# Optocoupler.net
KiCad netlist of a schematic drawn in Altium Designer
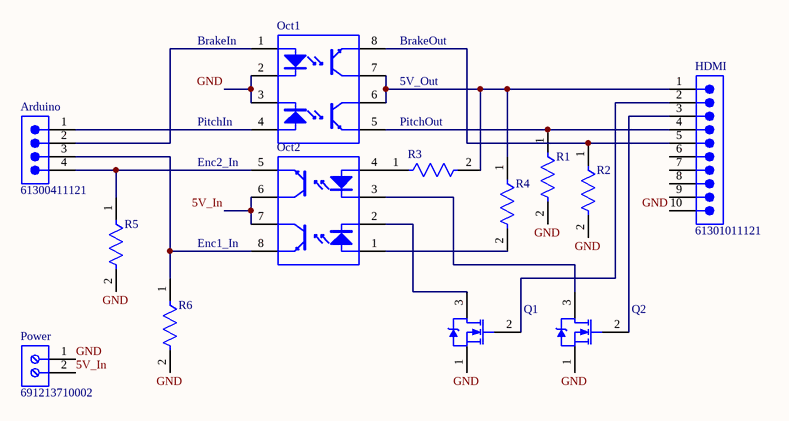
[diagram p0: Optocoupler.SchDoc]

(export (version "E")
  (design (tool "Eeschema 10.0.6"))
  (components
    (comp (ref "Arduino")
      (value "61300411121")
      (footprint "61300411121")
      (libsource (lib "Altium Content Vault") (part "Header_Male_1R_04P"))
    )
    (comp (ref "HDMI")
      (value "61301011121")
      (footprint "61301011121")
      (libsource (lib "Altium Content Vault") (part "Header_Male_1R_10P"))
    )
    (comp (ref "Oct1")
      (value "~")
      (footprint "VISH-DIP8")
      (description "Optocoupler, Phototransistor Output, Dual Channel, 1.3 V, -55 to 100 degC, 8-Pin DIP, RoHS, Tube")
      (fields (field (name "TOLERANCE") "1%"))
      (libsource (lib "Altium Content Vault") (part "OPTO-AKKAECCE-8"))
    )
    (comp (ref "Oct2")
      (value "~")
      (footprint "VISH-DIP8")
      (description "Optocoupler, Phototransistor Output, Dual Channel, 1.3 V, -55 to 100 degC, 8-Pin DIP, RoHS, Tube")
      (fields (field (name "TOLERANCE") "1%"))
      (libsource (lib "Altium Content Vault") (part "OPTO-AKKAECCE-8"))
    )
    (comp (ref "Power")
      (value "691213710002")
      (footprint "691213710002")
      (fields (field (name "VOLTAGE") "300V"))
      (libsource (lib "Altium Content Vault") (part "TBL - 1R - 02P - Screw"))
    )
    (comp (ref "Q1")
      (value "~")
      (footprint "ONSC-TO-92-3-29-11_AM_BL")
      (description "Small Signal MOSFET, 200 mA, 60 V, N-Channel, 3-Pin TO-92, Pb-Free, Tape and Reel")
      (fields (field (name "MANUFACTURER") "On Semiconductor") (field (name "PARTNUMBER") "2N7000RLRAG"))
      (libsource (lib "Altium Content Vault") (part "ONSC-NMOS-S1G2D3-3"))
    )
    (comp (ref "Q2")
      (value "~")
      (footprint "ONSC-TO-92-3-29-11_AM_BL")
      (description "Small Signal MOSFET, 200 mA, 60 V, N-Channel, 3-Pin TO-92, Pb-Free, Tape and Reel")
      (fields (field (name "MANUFACTURER") "On Semiconductor") (field (name "PARTNUMBER") "2N7000RLRAG"))
      (libsource (lib "Altium Content Vault") (part "ONSC-NMOS-S1G2D3-3"))
    )
    (comp (ref "R1")
      (value "~")
      (footprint "FP-MRS25-MFG")
      (fields (field (name "TOLERANCE") "1%"))
      (libsource (lib "Altium Content Vault") (part "1029c3af85768c4190bb7ad29bc67b5"))
    )
    (comp (ref "R2")
      (value "~")
      (footprint "FP-MRS25-MFG")
      (fields (field (name "TOLERANCE") "1%"))
      (libsource (lib "Altium Content Vault") (part "1029c3af85768c4190bb7ad29bc67b5"))
    )
    (comp (ref "R3")
      (value "~")
      (footprint "FP-MRS25-MFG")
      (fields (field (name "TOLERANCE") "1%"))
      (libsource (lib "Altium Content Vault") (part "1029c3af85768c4190bb7ad29bc67b5"))
    )
    (comp (ref "R4")
      (value "~")
      (footprint "FP-MRS25-MFG")
      (fields (field (name "TOLERANCE") "1%"))
      (libsource (lib "Altium Content Vault") (part "1029c3af85768c4190bb7ad29bc67b5"))
    )
    (comp (ref "R5")
      (value "~")
      (footprint "FP-MRS25-MFG")
      (fields (field (name "TOLERANCE") "1%"))
      (libsource (lib "Altium Content Vault") (part "1029c3af85768c4190bb7ad29bc67b5"))
    )
    (comp (ref "R6")
      (value "~")
      (footprint "FP-MRS25-MFG")
      (fields (field (name "TOLERANCE") "1%"))
      (libsource (lib "Altium Content Vault") (part "1029c3af85768c4190bb7ad29bc67b5"))
    )
  )
  (nets
    (net (code "1") (name "/5V_In") (class "Default")
      (node (ref "Oct2") (pin "6") (pinfunction "C_6") (pintype "passive"))
      (node (ref "Oct2") (pin "7") (pinfunction "C_7") (pintype "passive"))
      (node (ref "Power") (pin "2") (pinfunction "2_2") (pintype "passive"))
    )
    (net (code "2") (name "/GND") (class "Default")
      (node (ref "HDMI") (pin "10") (pinfunction "10_10") (pintype "passive"))
      (node (ref "Oct1") (pin "2") (pinfunction "C_2") (pintype "passive"))
      (node (ref "Oct1") (pin "3") (pinfunction "C_3") (pintype "passive"))
      (node (ref "Power") (pin "1") (pinfunction "1_1") (pintype "passive"))
      (node (ref "Q1") (pin "1") (pinfunction "S_1") (pintype "passive"))
      (node (ref "Q2") (pin "1") (pinfunction "S_1") (pintype "passive"))
      (node (ref "R1") (pin "2") (pinfunction "2_2") (pintype "passive"))
      (node (ref "R2") (pin "2") (pinfunction "2_2") (pintype "passive"))
      (node (ref "R5") (pin "2") (pinfunction "2_2") (pintype "passive"))
      (node (ref "R6") (pin "2") (pinfunction "2_2") (pintype "passive"))
    )
    (net (code "3") (name "Net-(Arduino-Pad1)") (class "Default")
      (node (ref "Arduino") (pin "1") (pinfunction "1_1") (pintype "passive"))
      (node (ref "Oct1") (pin "4") (pinfunction "A_4") (pintype "passive"))
    )
    (net (code "4") (name "Net-(Arduino-Pad2)") (class "Default")
      (node (ref "Arduino") (pin "2") (pinfunction "2_2") (pintype "passive"))
      (node (ref "Oct1") (pin "1") (pinfunction "A_1") (pintype "passive"))
    )
    (net (code "5") (name "Net-(Arduino-Pad3)") (class "Default")
      (node (ref "Arduino") (pin "3") (pinfunction "3_3") (pintype "passive"))
      (node (ref "Oct2") (pin "8") (pinfunction "E_8") (pintype "passive"))
      (node (ref "R6") (pin "1") (pinfunction "1_1") (pintype "passive"))
    )
    (net (code "6") (name "Net-(Arduino-Pad4)") (class "Default")
      (node (ref "Arduino") (pin "4") (pinfunction "4_4") (pintype "passive"))
      (node (ref "Oct2") (pin "5") (pinfunction "E_5") (pintype "passive"))
      (node (ref "R5") (pin "1") (pinfunction "1_1") (pintype "passive"))
    )
    (net (code "7") (name "Net-(HDMI-Pad1)") (class "Default")
      (node (ref "HDMI") (pin "1") (pinfunction "1_1") (pintype "passive"))
      (node (ref "Oct1") (pin "6") (pinfunction "C_6") (pintype "passive"))
      (node (ref "Oct1") (pin "7") (pinfunction "C_7") (pintype "passive"))
      (node (ref "R3") (pin "2") (pinfunction "2_2") (pintype "passive"))
      (node (ref "R4") (pin "1") (pinfunction "1_1") (pintype "passive"))
    )
    (net (code "8") (name "Net-(HDMI-Pad4)") (class "Default")
      (node (ref "HDMI") (pin "4") (pinfunction "4_4") (pintype "passive"))
      (node (ref "Oct1") (pin "5") (pinfunction "E_5") (pintype "passive"))
      (node (ref "R1") (pin "1") (pinfunction "1_1") (pintype "passive"))
    )
    (net (code "9") (name "Net-(HDMI-Pad5)") (class "Default")
      (node (ref "HDMI") (pin "5") (pinfunction "5_5") (pintype "passive"))
      (node (ref "Oct1") (pin "8") (pinfunction "E_8") (pintype "passive"))
      (node (ref "R2") (pin "1") (pinfunction "1_1") (pintype "passive"))
    )
    (net (code "10") (name "Net-(Oct2-A-Pad1)") (class "Default")
      (node (ref "Oct2") (pin "1") (pinfunction "A_1") (pintype "passive"))
      (node (ref "R4") (pin "2") (pinfunction "2_2") (pintype "passive"))
    )
    (net (code "11") (name "Net-(Oct2-A-Pad4)") (class "Default")
      (node (ref "Oct2") (pin "4") (pinfunction "A_4") (pintype "passive"))
      (node (ref "R3") (pin "1") (pinfunction "1_1") (pintype "passive"))
    )
    (net (code "12") (name "Net-(Q1-D)") (class "Default")
      (node (ref "Oct2") (pin "2") (pinfunction "C_2") (pintype "passive"))
      (node (ref "Q1") (pin "3") (pinfunction "D_3") (pintype "passive"))
    )
    (net (code "13") (name "Net-(Q1-G)") (class "Default")
      (node (ref "HDMI") (pin "2") (pinfunction "2_2") (pintype "passive"))
      (node (ref "Q1") (pin "2") (pinfunction "G_2") (pintype "passive"))
    )
    (net (code "14") (name "Net-(Q2-D)") (class "Default")
      (node (ref "Oct2") (pin "3") (pinfunction "C_3") (pintype "passive"))
      (node (ref "Q2") (pin "3") (pinfunction "D_3") (pintype "passive"))
    )
    (net (code "15") (name "Net-(Q2-G)") (class "Default")
      (node (ref "HDMI") (pin "3") (pinfunction "3_3") (pintype "passive"))
      (node (ref "Q2") (pin "2") (pinfunction "G_2") (pintype "passive"))
    )
    (net (code "16") (name "unconnected-(HDMI-Pad6)") (class "Default")
      (node (ref "HDMI") (pin "6") (pinfunction "6_6") (pintype "passive"))
    )
    (net (code "17") (name "unconnected-(HDMI-Pad7)") (class "Default")
      (node (ref "HDMI") (pin "7") (pinfunction "7_7") (pintype "passive"))
    )
    (net (code "18") (name "unconnected-(HDMI-Pad8)") (class "Default")
      (node (ref "HDMI") (pin "8") (pinfunction "8_8") (pintype "passive"))
    )
    (net (code "19") (name "unconnected-(HDMI-Pad9)") (class "Default")
      (node (ref "HDMI") (pin "9") (pinfunction "9_9") (pintype "passive"))
    )
  )
)
